# STM32L431RCT6-BASIC.net
KiCad netlist of a schematic drawn in Altium Designer
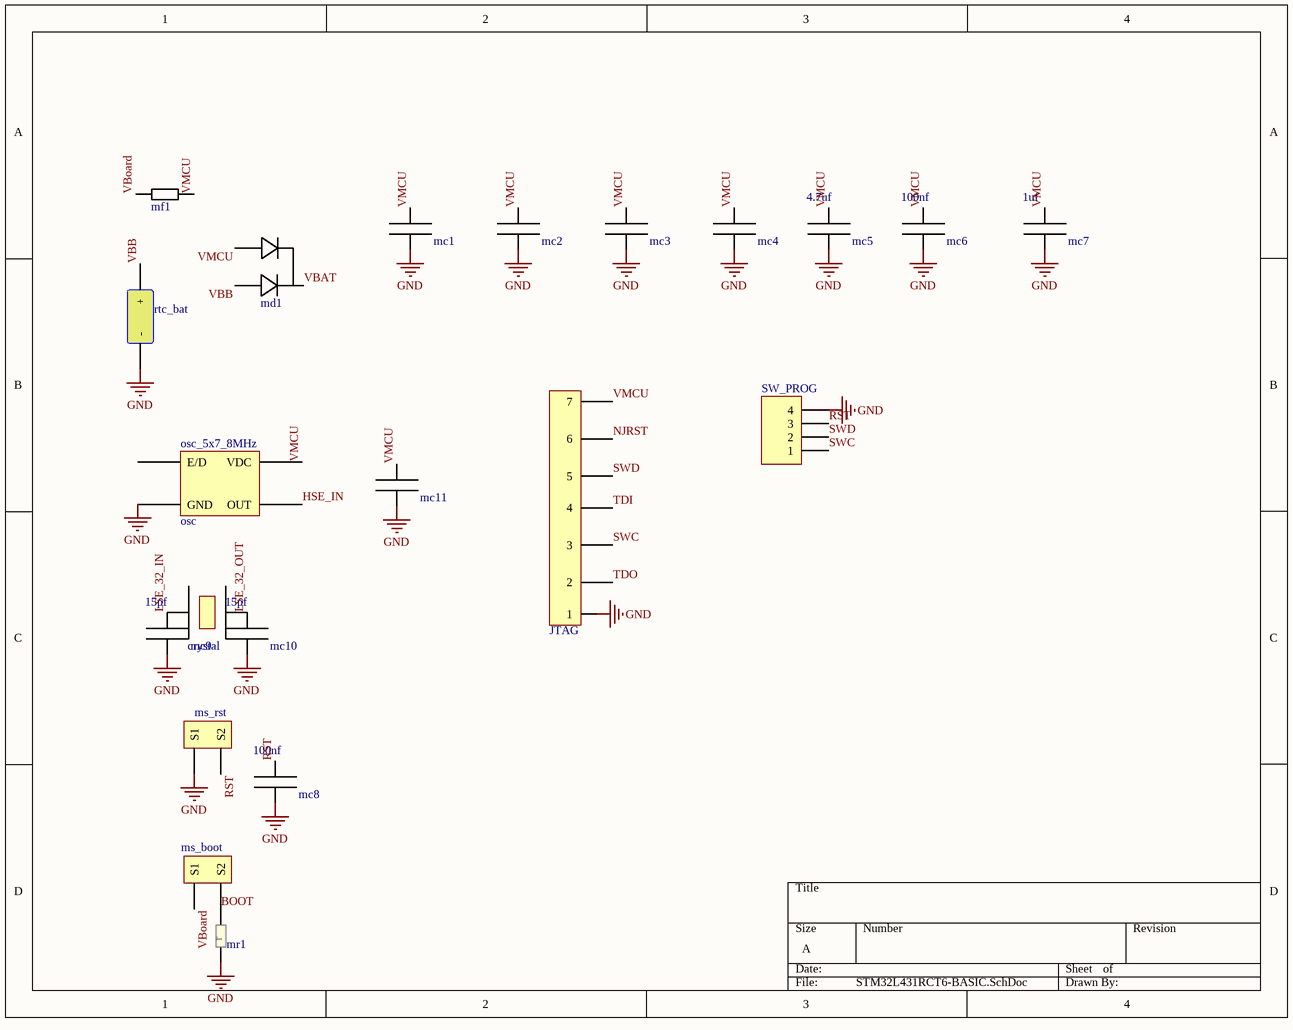
[diagram p0: STM32L431RCT6-BASIC.SchDoc]

(export (version "E")
  (design (tool "Eeschema 10.0.6"))
  (components
    (comp (ref "crystal_smd_32k")
      (value "crystal")
      (footprint "abr_crystal_cm405_32k_3d")
      (libsource (lib "abr_crystal_osc_96_02") (part "abr_crystal_smd_32K"))
    )
    (comp (ref "JTAG")
      (value "pin header 2mm")
      (footprint "abr_ph_1x7_2mm_2d_female")
      (libsource (lib "lpwireless") (part "abr_1x7_2mm"))
    )
    (comp (ref "mc1")
      (value "100nf")
      (footprint "abr_cap_0805_3d")
      (libsource (lib "abr_smd_0805_all") (part "abr_cap_0805"))
    )
    (comp (ref "mc2")
      (value "100nf")
      (footprint "abr_cap_0805_3d")
      (libsource (lib "abr_smd_0805_all") (part "abr_cap_0805"))
    )
    (comp (ref "mc3")
      (value "100nf")
      (footprint "abr_cap_0805_3d")
      (libsource (lib "abr_smd_0805_all") (part "abr_cap_0805"))
    )
    (comp (ref "mc4")
      (value "100nf")
      (footprint "abr_cap_0805_3d")
      (libsource (lib "abr_smd_0805_all") (part "abr_cap_0805"))
    )
    (comp (ref "mc5")
      (value "4.7uf")
      (footprint "abr_cap_0805_3d")
      (libsource (lib "abr_smd_0805_all") (part "abr_cap_0805"))
    )
    (comp (ref "mc6")
      (value "100nf")
      (footprint "abr_cap_0805_3d")
      (libsource (lib "abr_smd_0805_all") (part "abr_cap_0805"))
    )
    (comp (ref "mc7")
      (value "1uf")
      (footprint "abr_cap_0805_3d")
      (libsource (lib "abr_smd_0805_all") (part "abr_cap_0805"))
    )
    (comp (ref "mc8")
      (value "100nf")
      (footprint "abr_cap_0805_3d")
      (libsource (lib "abr_smd_0805_all") (part "abr_cap_0805"))
    )
    (comp (ref "mc9")
      (value "15pf")
      (footprint "abr_cap_0805_3d")
      (libsource (lib "abr_smd_0805_all") (part "abr_cap_0805"))
    )
    (comp (ref "mc10")
      (value "15pf")
      (footprint "abr_cap_0805_3d")
      (libsource (lib "abr_smd_0805_all") (part "abr_cap_0805"))
    )
    (comp (ref "mc11")
      (value "100nf")
      (footprint "abr_cap_0805_3d")
      (libsource (lib "abr_smd_0805_all") (part "abr_cap_0805"))
    )
    (comp (ref "md1")
      (value "abr_diode_shotkey")
      (footprint "abr_diode_bat54c_3d")
      (libsource (lib "abr_diode_smd") (part "abr_diode_shatkey_bat54c"))
    )
    (comp (ref "mf1")
      (value "smd-0805")
      (footprint "abr_fer_0805_3d")
      (libsource (lib "abr_smd_0805_all") (part "abr_fer_0805"))
    )
    (comp (ref "mr1")
      (value "10k")
      (footprint "abr_res_0805_3d")
      (libsource (lib "abr_smd_0805_all") (part "abr_res_0805"))
    )
    (comp (ref "ms_boot")
      (value "switch")
      (footprint "abr_sw_tact_3d")
      (libsource (lib "abr_switch") (part "abr_switch_tact"))
    )
    (comp (ref "ms_rst")
      (value "switch")
      (footprint "abr_sw_tact_3d")
      (libsource (lib "abr_switch") (part "abr_switch_tact"))
    )
    (comp (ref "osc_5x7_8MHz")
      (value "osc")
      (footprint "abr_osc_5x7_3d")
      (libsource (lib "abr_crystal_osc_96_02") (part "abr_osc_5x7"))
    )
    (comp (ref "rtc_bat")
      (value "battery holder")
      (footprint "abr_bh_cr1220_3d")
      (libsource (lib "abr_battery_related_96_02") (part "abr_bh_rtc"))
    )
    (comp (ref "SW_PROG")
      (value "Header 4")
      (footprint "HDR1X4")
      (description "Header, 4-Pin")
      (fields (field (name "PUBLISHER") "Altium Limited"))
      (libsource (lib "Miscellaneous Connectors") (part "Header 4"))
    )
  )
  (nets
    (net (code "1") (name "/BOOT") (class "Default")
      (node (ref "mr1") (pin "1") (pinfunction "0_1") (pintype "passive"))
      (node (ref "ms_boot") (pin "2") (pinfunction "S2_2") (pintype "passive"))
    )
    (net (code "2") (name "/HSE_IN") (class "Default")
      (node (ref "osc_5x7_8MHz") (pin "3") (pinfunction "OUT_3") (pintype "passive"))
    )
    (net (code "3") (name "/LSE_32_IN") (class "Default")
      (node (ref "crystal_smd_32k") (pin "1") (pintype "passive"))
      (node (ref "mc9") (pin "1") (pinfunction "10_1") (pintype "passive"))
    )
    (net (code "4") (name "/LSE_32_OUT") (class "Default")
      (node (ref "crystal_smd_32k") (pin "2") (pintype "passive"))
      (node (ref "mc10") (pin "1") (pinfunction "10_1") (pintype "passive"))
    )
    (net (code "5") (name "/NJRST") (class "Default")
      (node (ref "JTAG") (pin "6") (pinfunction "6_6") (pintype "passive"))
    )
    (net (code "6") (name "/RST") (class "Default")
      (node (ref "SW_PROG") (pin "3") (pinfunction "3_3") (pintype "passive"))
      (node (ref "mc8") (pin "1") (pinfunction "10_1") (pintype "passive"))
      (node (ref "ms_rst") (pin "2") (pinfunction "S2_2") (pintype "passive"))
    )
    (net (code "7") (name "/SWC") (class "Default")
      (node (ref "JTAG") (pin "3") (pinfunction "3_3") (pintype "passive"))
      (node (ref "SW_PROG") (pin "1") (pinfunction "1_1") (pintype "passive"))
    )
    (net (code "8") (name "/SWD") (class "Default")
      (node (ref "JTAG") (pin "5") (pinfunction "5_5") (pintype "passive"))
      (node (ref "SW_PROG") (pin "2") (pinfunction "2_2") (pintype "passive"))
    )
    (net (code "9") (name "/TDI") (class "Default")
      (node (ref "JTAG") (pin "4") (pinfunction "4_4") (pintype "passive"))
    )
    (net (code "10") (name "/TDO") (class "Default")
      (node (ref "JTAG") (pin "2") (pinfunction "2_2") (pintype "passive"))
    )
    (net (code "11") (name "/VBAT") (class "Default")
      (node (ref "md1") (pin "3") (pinfunction "5_3") (pintype "passive"))
    )
    (net (code "12") (name "/VBB") (class "Default")
      (node (ref "md1") (pin "2") (pinfunction "2_2") (pintype "passive"))
      (node (ref "rtc_bat") (pin "1") (pinfunction "+_1") (pintype "passive"))
    )
    (net (code "13") (name "/VBoard") (class "Default")
      (node (ref "mf1") (pin "0") (pinfunction "1_0") (pintype "passive"))
      (node (ref "ms_boot") (pin "1") (pinfunction "S1_1") (pintype "passive"))
    )
    (net (code "14") (name "/VMCU") (class "Default")
      (node (ref "JTAG") (pin "7") (pinfunction "7_7") (pintype "passive"))
      (node (ref "mc1") (pin "1") (pinfunction "10_1") (pintype "passive"))
      (node (ref "mc11") (pin "1") (pinfunction "10_1") (pintype "passive"))
      (node (ref "mc2") (pin "1") (pinfunction "10_1") (pintype "passive"))
      (node (ref "mc3") (pin "1") (pinfunction "10_1") (pintype "passive"))
      (node (ref "mc4") (pin "1") (pinfunction "10_1") (pintype "passive"))
      (node (ref "mc5") (pin "1") (pinfunction "10_1") (pintype "passive"))
      (node (ref "mc6") (pin "1") (pinfunction "10_1") (pintype "passive"))
      (node (ref "mc7") (pin "1") (pinfunction "10_1") (pintype "passive"))
      (node (ref "md1") (pin "1") (pinfunction "4_1") (pintype "passive"))
      (node (ref "mf1") (pin "1") (pinfunction "2_1") (pintype "passive"))
      (node (ref "osc_5x7_8MHz") (pin "4") (pinfunction "VDC_4") (pintype "passive"))
    )
    (net (code "15") (name "GND") (class "Default")
      (node (ref "JTAG") (pin "1") (pinfunction "1_1") (pintype "passive"))
      (node (ref "SW_PROG") (pin "4") (pinfunction "4_4") (pintype "passive"))
      (node (ref "mc1") (pin "0") (pinfunction "2_0") (pintype "passive"))
      (node (ref "mc10") (pin "0") (pinfunction "2_0") (pintype "passive"))
      (node (ref "mc11") (pin "0") (pinfunction "2_0") (pintype "passive"))
      (node (ref "mc2") (pin "0") (pinfunction "2_0") (pintype "passive"))
      (node (ref "mc3") (pin "0") (pinfunction "2_0") (pintype "passive"))
      (node (ref "mc4") (pin "0") (pinfunction "2_0") (pintype "passive"))
      (node (ref "mc5") (pin "0") (pinfunction "2_0") (pintype "passive"))
      (node (ref "mc6") (pin "0") (pinfunction "2_0") (pintype "passive"))
      (node (ref "mc7") (pin "0") (pinfunction "2_0") (pintype "passive"))
      (node (ref "mc8") (pin "0") (pinfunction "2_0") (pintype "passive"))
      (node (ref "mc9") (pin "0") (pinfunction "2_0") (pintype "passive"))
      (node (ref "mr1") (pin "0") (pinfunction "0_0") (pintype "passive"))
      (node (ref "ms_rst") (pin "1") (pinfunction "S1_1") (pintype "passive"))
      (node (ref "osc_5x7_8MHz") (pin "2") (pinfunction "GND_2") (pintype "passive"))
      (node (ref "rtc_bat") (pin "2") (pinfunction "-_2") (pintype "passive"))
    )
    (net (code "16") (name "unconnected-(osc_5x7_8MHz-E{slash}D-Pad1)") (class "Default")
      (node (ref "osc_5x7_8MHz") (pin "1") (pinfunction "E/D_1") (pintype "passive"))
    )
  )
)
